# VX1010.net
KiCad netlist of a schematic drawn in EasyEDA
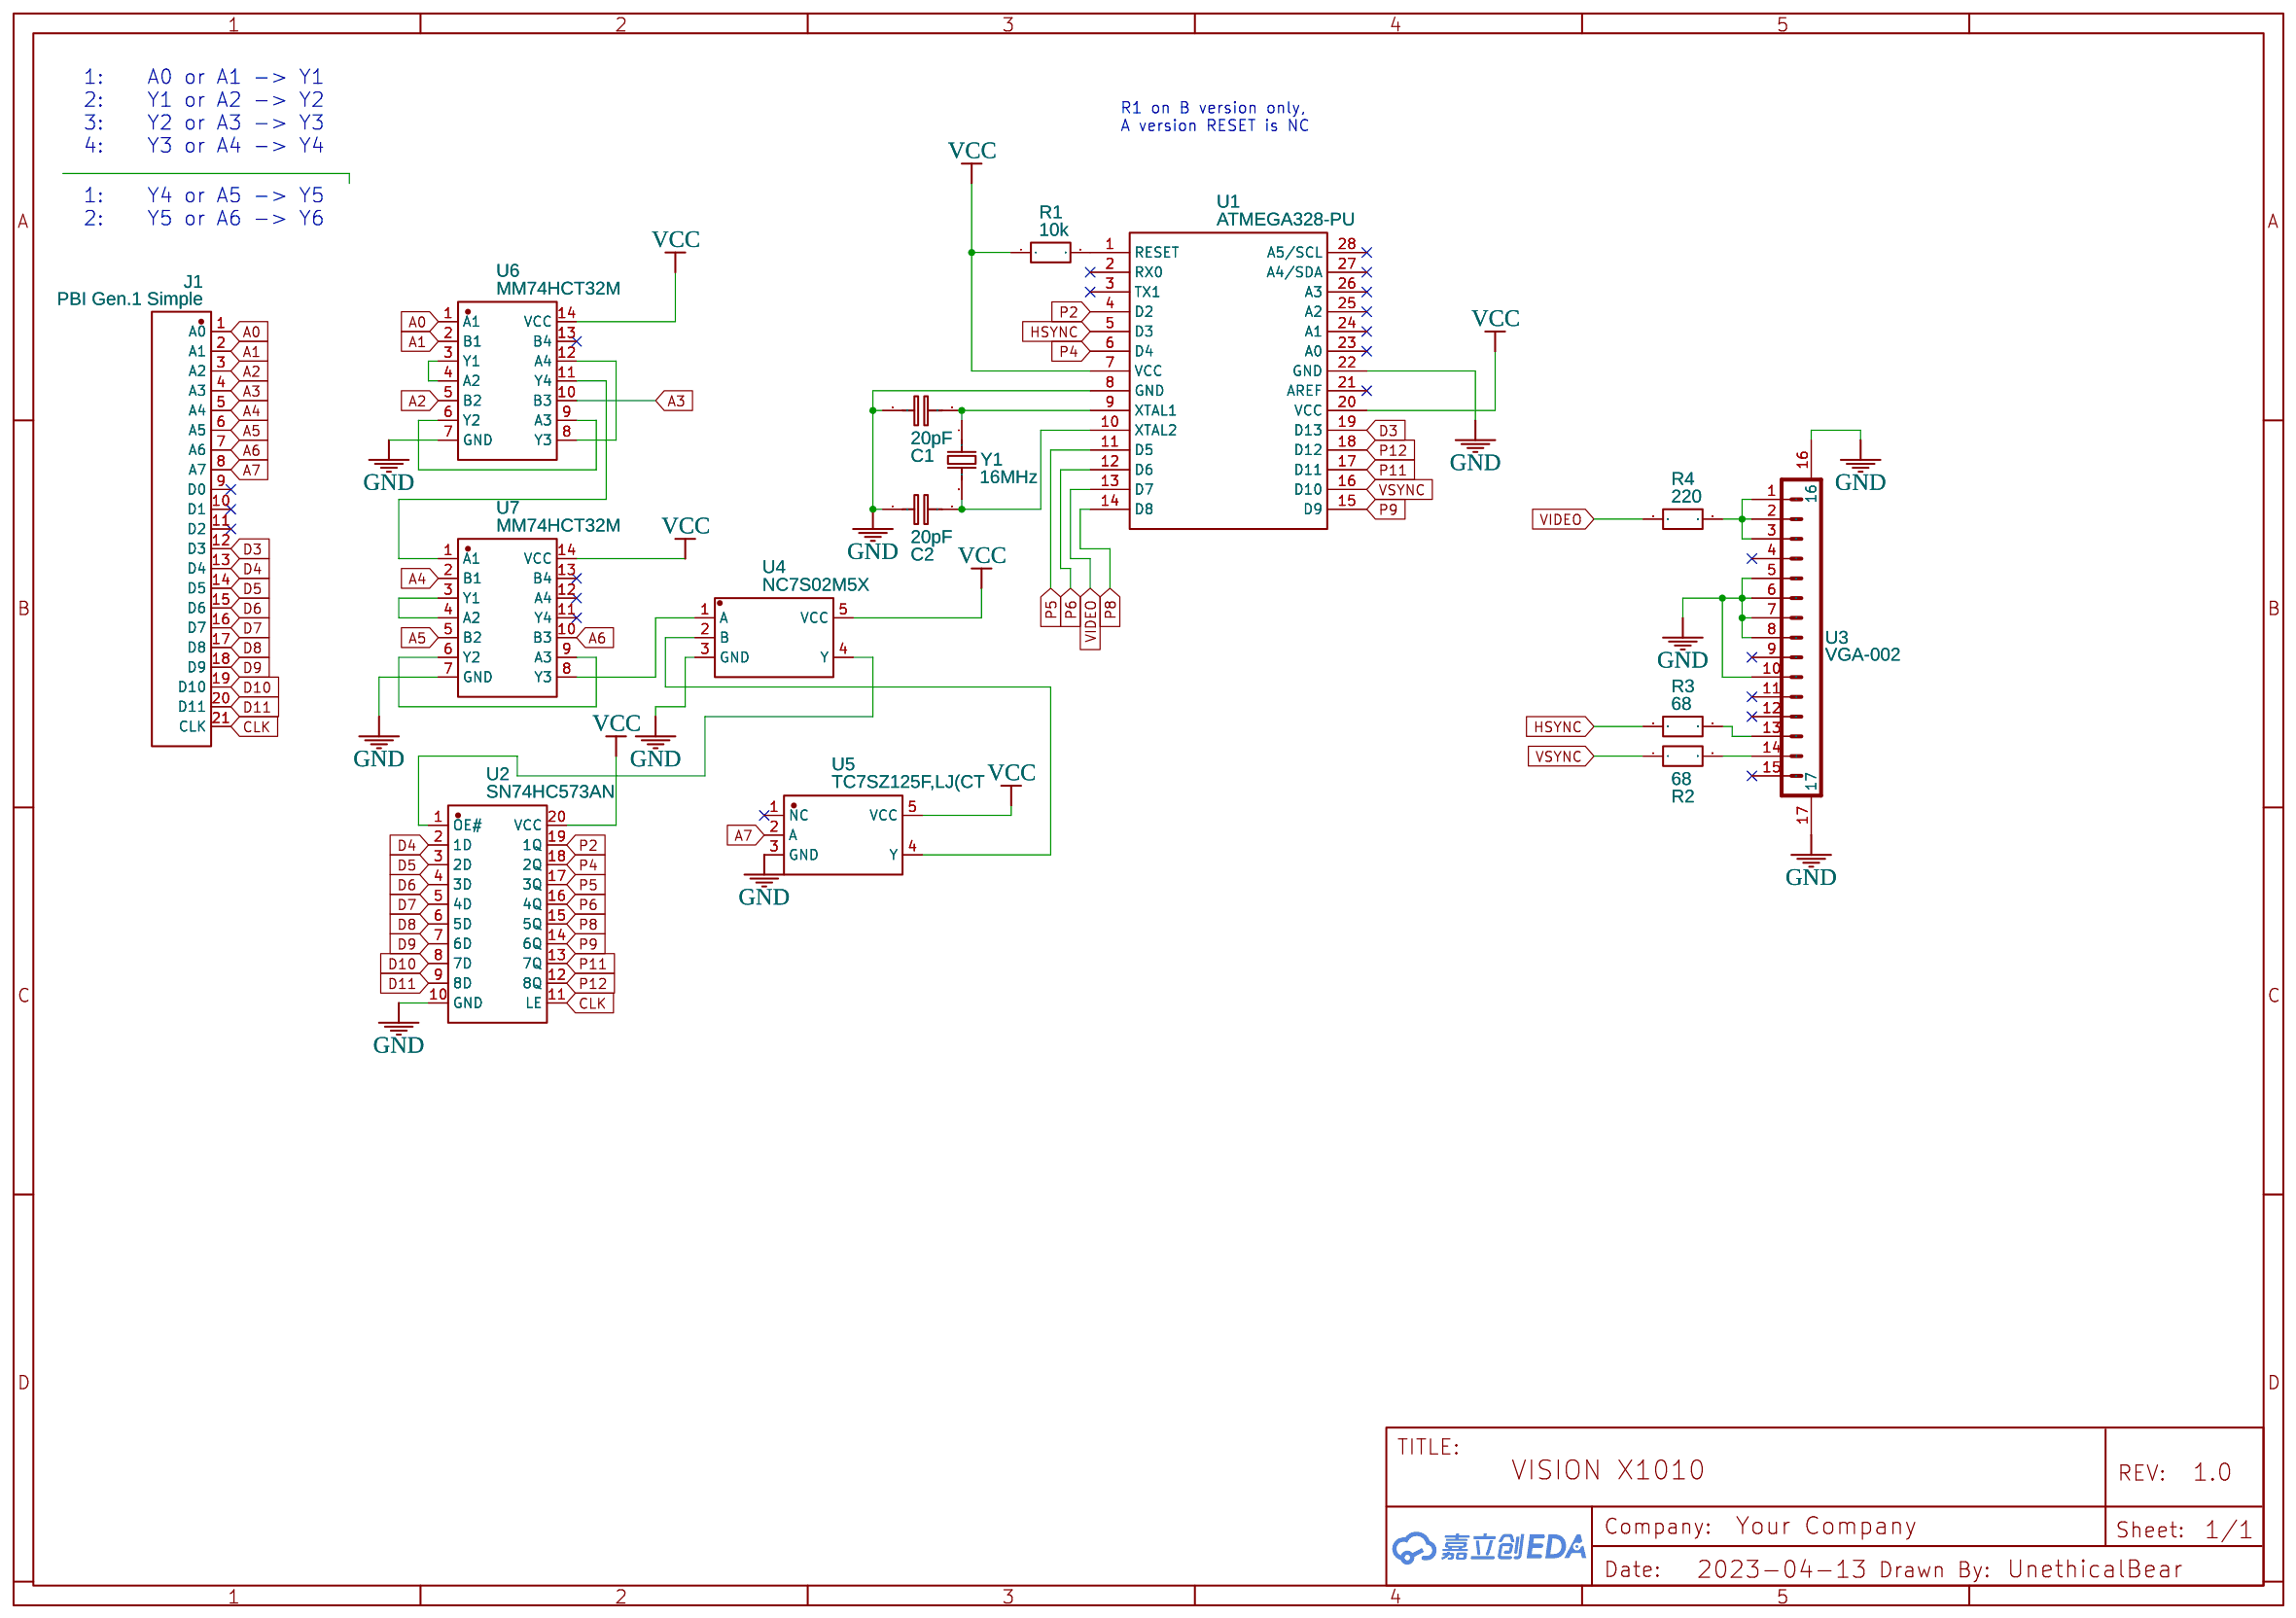
[diagram p0: schematic sheet]

(export (version "E")
  (design (tool "Eeschema 10.0.6"))
  (components
    (comp (ref "C1") (value "20pF") (libsource (lib "") (part "C_RAD-0.1_EU")))
    (comp (ref "C2") (value "20pF") (libsource (lib "") (part "C_RAD-0.1_EU")))
    (comp (ref "J1") (value "PBI Gen.1 Simple") (libsource (lib "") (part "PBI Gen.1 Simple")))
    (comp (ref "R1") (value "10k") (libsource (lib "") (part "R_AXIAL-0.3_EU")))
    (comp (ref "R2") (value "68") (libsource (lib "") (part "R_AXIAL-0.3_EU")))
    (comp (ref "R3") (value "68") (libsource (lib "") (part "R_AXIAL-0.3_EU")))
    (comp (ref "R4") (value "220") (libsource (lib "") (part "R_AXIAL-0.3_EU")))
    (comp (ref "U1") (value "ATMEGA328-PU") (libsource (lib "") (part "ATMEGA328-PU 28 PINSET")))
    (comp (ref "U2")
      (value "SN74HC573AN")
      (fields (field (name "Manufacturer") "TI"))
      (libsource (lib "") (part "SN74HC573AN"))
    )
    (comp (ref "U3")
      (value "VGA-002")
      (fields (field (name "Manufacturer") "BOOMELE(博穆精密)"))
      (libsource (lib "") (part "VGA-002"))
    )
    (comp (ref "U4")
      (value "NC7S02M5X")
      (fields (field (name "Manufacturer") "onsemi(安森美)"))
      (libsource (lib "") (part "NC7S02M5X"))
    )
    (comp (ref "U5")
      (value "TC7SZ125F,LJ(CT")
      (fields (field (name "Manufacturer") "TOSHIBA(东芝)"))
      (libsource (lib "") (part "TC7SZ125F,LJ(CT"))
    )
    (comp (ref "U6")
      (value "MM74HCT32M")
      (fields (field (name "Manufacturer") "onsemi(安森美)"))
      (libsource (lib "") (part "MM74HCT32M"))
    )
    (comp (ref "U7")
      (value "MM74HCT32M")
      (fields (field (name "Manufacturer") "onsemi(安森美)"))
      (libsource (lib "") (part "MM74HCT32M"))
    )
    (comp (ref "Y1")
      (value "16MHz")
      (fields (field (name "Manufacturer Part") "ABL-16.000MHZ-B2") (field (name "Manufacturer") "ABRACON"))
      (libsource (lib "") (part "X49SSM16MSD2SI"))
    )
  )
  (nets
    (net (code "1") (name "A0") (class "Default")
      (node (ref "J1") (pin "1") (pinfunction "A0_1") (pintype "unspecified"))
      (node (ref "U6") (pin "1") (pinfunction "A1_1") (pintype "unspecified"))
    )
    (net (code "2") (name "A1") (class "Default")
      (node (ref "J1") (pin "2") (pinfunction "A1_2") (pintype "unspecified"))
      (node (ref "U6") (pin "2") (pinfunction "B1_2") (pintype "unspecified"))
    )
    (net (code "3") (name "A2") (class "Default")
      (node (ref "J1") (pin "3") (pinfunction "A2_3") (pintype "unspecified"))
      (node (ref "U6") (pin "5") (pinfunction "B2_5") (pintype "unspecified"))
    )
    (net (code "4") (name "A3") (class "Default")
      (node (ref "J1") (pin "4") (pinfunction "A3_4") (pintype "unspecified"))
      (node (ref "U6") (pin "10") (pinfunction "B3_10") (pintype "unspecified"))
    )
    (net (code "5") (name "A4") (class "Default")
      (node (ref "J1") (pin "5") (pinfunction "A4_5") (pintype "unspecified"))
      (node (ref "U7") (pin "2") (pinfunction "B1_2") (pintype "unspecified"))
    )
    (net (code "6") (name "A5") (class "Default")
      (node (ref "J1") (pin "6") (pinfunction "A5_6") (pintype "unspecified"))
      (node (ref "U7") (pin "5") (pinfunction "B2_5") (pintype "unspecified"))
    )
    (net (code "7") (name "A6") (class "Default")
      (node (ref "J1") (pin "7") (pinfunction "A6_7") (pintype "unspecified"))
      (node (ref "U7") (pin "10") (pinfunction "B3_10") (pintype "unspecified"))
    )
    (net (code "8") (name "A7") (class "Default")
      (node (ref "J1") (pin "8") (pinfunction "A7_8") (pintype "unspecified"))
      (node (ref "U5") (pin "2") (pinfunction "A_2") (pintype "unspecified"))
    )
    (net (code "9") (name "CLK") (class "Default")
      (node (ref "J1") (pin "21") (pinfunction "CLK_21") (pintype "unspecified"))
      (node (ref "U2") (pin "11") (pinfunction "LE_11") (pintype "unspecified"))
    )
    (net (code "10") (name "D3") (class "Default")
      (node (ref "J1") (pin "12") (pinfunction "D3_12") (pintype "unspecified"))
      (node (ref "U1") (pin "19") (pinfunction "D13_19") (pintype "unspecified"))
    )
    (net (code "11") (name "D4") (class "Default")
      (node (ref "J1") (pin "13") (pinfunction "D4_13") (pintype "unspecified"))
      (node (ref "U2") (pin "2") (pinfunction "1D_2") (pintype "unspecified"))
    )
    (net (code "12") (name "D5") (class "Default")
      (node (ref "J1") (pin "14") (pinfunction "D5_14") (pintype "unspecified"))
      (node (ref "U2") (pin "3") (pinfunction "2D_3") (pintype "unspecified"))
    )
    (net (code "13") (name "D6") (class "Default")
      (node (ref "J1") (pin "15") (pinfunction "D6_15") (pintype "unspecified"))
      (node (ref "U2") (pin "4") (pinfunction "3D_4") (pintype "unspecified"))
    )
    (net (code "14") (name "D7") (class "Default")
      (node (ref "J1") (pin "16") (pinfunction "D7_16") (pintype "unspecified"))
      (node (ref "U2") (pin "5") (pinfunction "4D_5") (pintype "unspecified"))
    )
    (net (code "15") (name "D8") (class "Default")
      (node (ref "J1") (pin "17") (pinfunction "D8_17") (pintype "unspecified"))
      (node (ref "U2") (pin "6") (pinfunction "5D_6") (pintype "unspecified"))
    )
    (net (code "16") (name "D9") (class "Default")
      (node (ref "J1") (pin "18") (pinfunction "D9_18") (pintype "unspecified"))
      (node (ref "U2") (pin "7") (pinfunction "6D_7") (pintype "unspecified"))
    )
    (net (code "17") (name "D10") (class "Default")
      (node (ref "J1") (pin "19") (pinfunction "D10_19") (pintype "unspecified"))
      (node (ref "U2") (pin "8") (pinfunction "7D_8") (pintype "unspecified"))
    )
    (net (code "18") (name "D11") (class "Default")
      (node (ref "J1") (pin "20") (pinfunction "D11_20") (pintype "unspecified"))
      (node (ref "U2") (pin "9") (pinfunction "8D_9") (pintype "unspecified"))
    )
    (net (code "19") (name "GND") (class "Default")
      (node (ref "C1") (pin "1") (pinfunction "1_1") (pintype "unspecified"))
      (node (ref "C2") (pin "1") (pinfunction "1_1") (pintype "unspecified"))
      (node (ref "U1") (pin "22") (pinfunction "GND_22") (pintype "unspecified"))
      (node (ref "U1") (pin "8") (pinfunction "GND_8") (pintype "unspecified"))
      (node (ref "U2") (pin "10") (pinfunction "GND_10") (pintype "unspecified"))
      (node (ref "U3") (pin "10") (pinfunction "10_10") (pintype "unspecified"))
      (node (ref "U3") (pin "16") (pinfunction "16_16") (pintype "unspecified"))
      (node (ref "U3") (pin "17") (pinfunction "17_17") (pintype "unspecified"))
      (node (ref "U3") (pin "5") (pinfunction "5_5") (pintype "unspecified"))
      (node (ref "U3") (pin "6") (pinfunction "6_6") (pintype "unspecified"))
      (node (ref "U3") (pin "7") (pinfunction "7_7") (pintype "unspecified"))
      (node (ref "U3") (pin "8") (pinfunction "8_8") (pintype "unspecified"))
      (node (ref "U4") (pin "3") (pinfunction "GND_3") (pintype "unspecified"))
      (node (ref "U5") (pin "3") (pinfunction "GND_3") (pintype "unspecified"))
      (node (ref "U6") (pin "7") (pinfunction "GND_7") (pintype "unspecified"))
      (node (ref "U7") (pin "7") (pinfunction "GND_7") (pintype "unspecified"))
    )
    (net (code "20") (name "HSYNC") (class "Default")
      (node (ref "R3") (pin "1") (pinfunction "1_1") (pintype "unspecified"))
      (node (ref "U1") (pin "5") (pinfunction "D3_5") (pintype "unspecified"))
    )
    (net (code "21") (name "Net-(R2-Pad2)") (class "Default")
      (node (ref "R2") (pin "2") (pinfunction "2_2") (pintype "unspecified"))
      (node (ref "U3") (pin "14") (pinfunction "14_14") (pintype "unspecified"))
    )
    (net (code "22") (name "Net-(R3-Pad2)") (class "Default")
      (node (ref "R3") (pin "2") (pinfunction "2_2") (pintype "unspecified"))
      (node (ref "U3") (pin "13") (pinfunction "13_13") (pintype "unspecified"))
    )
    (net (code "23") (name "Net-(R4-Pad2)") (class "Default")
      (node (ref "R4") (pin "2") (pinfunction "2_2") (pintype "unspecified"))
      (node (ref "U3") (pin "1") (pinfunction "1_1") (pintype "unspecified"))
      (node (ref "U3") (pin "2") (pinfunction "2_2") (pintype "unspecified"))
      (node (ref "U3") (pin "3") (pinfunction "3_3") (pintype "unspecified"))
    )
    (net (code "24") (name "Net-(U1-RESET)") (class "Default")
      (node (ref "R1") (pin "2") (pinfunction "2_2") (pintype "unspecified"))
      (node (ref "U1") (pin "1") (pinfunction "RESET_1") (pintype "unspecified"))
    )
    (net (code "25") (name "Net-(U1-XTAL1)") (class "Default")
      (node (ref "C1") (pin "2") (pinfunction "2_2") (pintype "unspecified"))
      (node (ref "U1") (pin "9") (pinfunction "XTAL1_9") (pintype "unspecified"))
      (node (ref "Y1") (pin "1") (pinfunction "1_1") (pintype "unspecified"))
    )
    (net (code "26") (name "Net-(U1-XTAL2)") (class "Default")
      (node (ref "C2") (pin "2") (pinfunction "2_2") (pintype "unspecified"))
      (node (ref "U1") (pin "10") (pinfunction "XTAL2_10") (pintype "unspecified"))
      (node (ref "Y1") (pin "2") (pinfunction "2_2") (pintype "unspecified"))
    )
    (net (code "27") (name "Net-(U2-OE#)") (class "Default")
      (node (ref "U2") (pin "1") (pinfunction "OE#_1") (pintype "unspecified"))
      (node (ref "U4") (pin "4") (pinfunction "Y_4") (pintype "unspecified"))
    )
    (net (code "28") (name "Net-(U4-A)") (class "Default")
      (node (ref "U4") (pin "1") (pinfunction "A_1") (pintype "unspecified"))
      (node (ref "U7") (pin "8") (pinfunction "Y3_8") (pintype "unspecified"))
    )
    (net (code "29") (name "Net-(U4-B)") (class "Default")
      (node (ref "U4") (pin "2") (pinfunction "B_2") (pintype "unspecified"))
      (node (ref "U5") (pin "4") (pinfunction "Y_4") (pintype "unspecified"))
    )
    (net (code "30") (name "Net-(U6-A2)") (class "Default")
      (node (ref "U6") (pin "3") (pinfunction "Y1_3") (pintype "unspecified"))
      (node (ref "U6") (pin "4") (pinfunction "A2_4") (pintype "unspecified"))
    )
    (net (code "31") (name "Net-(U6-A3)") (class "Default")
      (node (ref "U6") (pin "6") (pinfunction "Y2_6") (pintype "unspecified"))
      (node (ref "U6") (pin "9") (pinfunction "A3_9") (pintype "unspecified"))
    )
    (net (code "32") (name "Net-(U6-A4)") (class "Default")
      (node (ref "U6") (pin "12") (pinfunction "A4_12") (pintype "unspecified"))
      (node (ref "U6") (pin "8") (pinfunction "Y3_8") (pintype "unspecified"))
    )
    (net (code "33") (name "Net-(U6-Y4)") (class "Default")
      (node (ref "U6") (pin "11") (pinfunction "Y4_11") (pintype "unspecified"))
      (node (ref "U7") (pin "1") (pinfunction "A1_1") (pintype "unspecified"))
    )
    (net (code "34") (name "Net-(U7-A2)") (class "Default")
      (node (ref "U7") (pin "3") (pinfunction "Y1_3") (pintype "unspecified"))
      (node (ref "U7") (pin "4") (pinfunction "A2_4") (pintype "unspecified"))
    )
    (net (code "35") (name "Net-(U7-A3)") (class "Default")
      (node (ref "U7") (pin "6") (pinfunction "Y2_6") (pintype "unspecified"))
      (node (ref "U7") (pin "9") (pinfunction "A3_9") (pintype "unspecified"))
    )
    (net (code "36") (name "P2") (class "Default")
      (node (ref "U1") (pin "4") (pinfunction "D2_4") (pintype "unspecified"))
      (node (ref "U2") (pin "19") (pinfunction "1Q_19") (pintype "unspecified"))
    )
    (net (code "37") (name "P4") (class "Default")
      (node (ref "U1") (pin "6") (pinfunction "D4_6") (pintype "unspecified"))
      (node (ref "U2") (pin "18") (pinfunction "2Q_18") (pintype "unspecified"))
    )
    (net (code "38") (name "P5") (class "Default")
      (node (ref "U1") (pin "11") (pinfunction "D5_11") (pintype "unspecified"))
      (node (ref "U2") (pin "17") (pinfunction "3Q_17") (pintype "unspecified"))
    )
    (net (code "39") (name "P6") (class "Default")
      (node (ref "U1") (pin "12") (pinfunction "D6_12") (pintype "unspecified"))
      (node (ref "U2") (pin "16") (pinfunction "4Q_16") (pintype "unspecified"))
    )
    (net (code "40") (name "P8") (class "Default")
      (node (ref "U1") (pin "14") (pinfunction "D8_14") (pintype "unspecified"))
      (node (ref "U2") (pin "15") (pinfunction "5Q_15") (pintype "unspecified"))
    )
    (net (code "41") (name "P9") (class "Default")
      (node (ref "U1") (pin "15") (pinfunction "D9_15") (pintype "unspecified"))
      (node (ref "U2") (pin "14") (pinfunction "6Q_14") (pintype "unspecified"))
    )
    (net (code "42") (name "P11") (class "Default")
      (node (ref "U1") (pin "17") (pinfunction "D11_17") (pintype "unspecified"))
      (node (ref "U2") (pin "13") (pinfunction "7Q_13") (pintype "unspecified"))
    )
    (net (code "43") (name "P12") (class "Default")
      (node (ref "U1") (pin "18") (pinfunction "D12_18") (pintype "unspecified"))
      (node (ref "U2") (pin "12") (pinfunction "8Q_12") (pintype "unspecified"))
    )
    (net (code "44") (name "VCC") (class "Default")
      (node (ref "R1") (pin "1") (pinfunction "1_1") (pintype "unspecified"))
      (node (ref "U1") (pin "20") (pinfunction "VCC_20") (pintype "unspecified"))
      (node (ref "U1") (pin "7") (pinfunction "VCC_7") (pintype "unspecified"))
      (node (ref "U2") (pin "20") (pinfunction "VCC_20") (pintype "unspecified"))
      (node (ref "U4") (pin "5") (pinfunction "VCC_5") (pintype "unspecified"))
      (node (ref "U5") (pin "5") (pinfunction "VCC_5") (pintype "unspecified"))
      (node (ref "U6") (pin "14") (pinfunction "VCC_14") (pintype "unspecified"))
      (node (ref "U7") (pin "14") (pinfunction "VCC_14") (pintype "unspecified"))
    )
    (net (code "45") (name "VIDEO") (class "Default")
      (node (ref "R4") (pin "1") (pinfunction "1_1") (pintype "unspecified"))
      (node (ref "U1") (pin "13") (pinfunction "D7_13") (pintype "unspecified"))
    )
    (net (code "46") (name "VSYNC") (class "Default")
      (node (ref "R2") (pin "1") (pinfunction "1_1") (pintype "unspecified"))
      (node (ref "U1") (pin "16") (pinfunction "D10_16") (pintype "unspecified"))
    )
    (net (code "47") (name "unconnected-(J1-D0-Pad9)") (class "Default")
      (node (ref "J1") (pin "9") (pinfunction "D0_9") (pintype "unspecified+no_connect"))
    )
    (net (code "48") (name "unconnected-(J1-D1-Pad10)") (class "Default")
      (node (ref "J1") (pin "10") (pinfunction "D1_10") (pintype "unspecified+no_connect"))
    )
    (net (code "49") (name "unconnected-(J1-D2-Pad11)") (class "Default")
      (node (ref "J1") (pin "11") (pinfunction "D2_11") (pintype "unspecified+no_connect"))
    )
    (net (code "50") (name "unconnected-(U1-A0-Pad23)") (class "Default")
      (node (ref "U1") (pin "23") (pinfunction "A0_23") (pintype "unspecified+no_connect"))
    )
    (net (code "51") (name "unconnected-(U1-A1-Pad24)") (class "Default")
      (node (ref "U1") (pin "24") (pinfunction "A1_24") (pintype "unspecified+no_connect"))
    )
    (net (code "52") (name "unconnected-(U1-A2-Pad25)") (class "Default")
      (node (ref "U1") (pin "25") (pinfunction "A2_25") (pintype "unspecified+no_connect"))
    )
    (net (code "53") (name "unconnected-(U1-A3-Pad26)") (class "Default")
      (node (ref "U1") (pin "26") (pinfunction "A3_26") (pintype "unspecified+no_connect"))
    )
    (net (code "54") (name "unconnected-(U1-A4{slash}SDA-Pad27)") (class "Default")
      (node (ref "U1") (pin "27") (pinfunction "A4/SDA_27") (pintype "unspecified+no_connect"))
    )
    (net (code "55") (name "unconnected-(U1-A5{slash}SCL-Pad28)") (class "Default")
      (node (ref "U1") (pin "28") (pinfunction "A5/SCL_28") (pintype "unspecified+no_connect"))
    )
    (net (code "56") (name "unconnected-(U1-AREF-Pad21)") (class "Default")
      (node (ref "U1") (pin "21") (pinfunction "AREF_21") (pintype "unspecified+no_connect"))
    )
    (net (code "57") (name "unconnected-(U1-RX0-Pad2)") (class "Default")
      (node (ref "U1") (pin "2") (pinfunction "RX0_2") (pintype "unspecified+no_connect"))
    )
    (net (code "58") (name "unconnected-(U1-TX1-Pad3)") (class "Default")
      (node (ref "U1") (pin "3") (pinfunction "TX1_3") (pintype "unspecified+no_connect"))
    )
    (net (code "59") (name "unconnected-(U3-Pad4)") (class "Default")
      (node (ref "U3") (pin "4") (pinfunction "4_4") (pintype "unspecified+no_connect"))
    )
    (net (code "60") (name "unconnected-(U3-Pad9)") (class "Default")
      (node (ref "U3") (pin "9") (pinfunction "9_9") (pintype "unspecified+no_connect"))
    )
    (net (code "61") (name "unconnected-(U3-Pad11)") (class "Default")
      (node (ref "U3") (pin "11") (pinfunction "11_11") (pintype "unspecified+no_connect"))
    )
    (net (code "62") (name "unconnected-(U3-Pad12)") (class "Default")
      (node (ref "U3") (pin "12") (pinfunction "12_12") (pintype "unspecified+no_connect"))
    )
    (net (code "63") (name "unconnected-(U3-Pad15)") (class "Default")
      (node (ref "U3") (pin "15") (pinfunction "15_15") (pintype "unspecified+no_connect"))
    )
    (net (code "64") (name "unconnected-(U5-NC-Pad1)") (class "Default")
      (node (ref "U5") (pin "1") (pinfunction "NC_1") (pintype "unspecified+no_connect"))
    )
    (net (code "65") (name "unconnected-(U6-B4-Pad13)") (class "Default")
      (node (ref "U6") (pin "13") (pinfunction "B4_13") (pintype "unspecified+no_connect"))
    )
    (net (code "66") (name "unconnected-(U7-A4-Pad12)") (class "Default")
      (node (ref "U7") (pin "12") (pinfunction "A4_12") (pintype "unspecified+no_connect"))
    )
    (net (code "67") (name "unconnected-(U7-B4-Pad13)") (class "Default")
      (node (ref "U7") (pin "13") (pinfunction "B4_13") (pintype "unspecified+no_connect"))
    )
    (net (code "68") (name "unconnected-(U7-Y4-Pad11)") (class "Default")
      (node (ref "U7") (pin "11") (pinfunction "Y4_11") (pintype "unspecified+no_connect"))
    )
  )
)
